# Main.net
KiCad netlist of a schematic drawn in Altium Designer
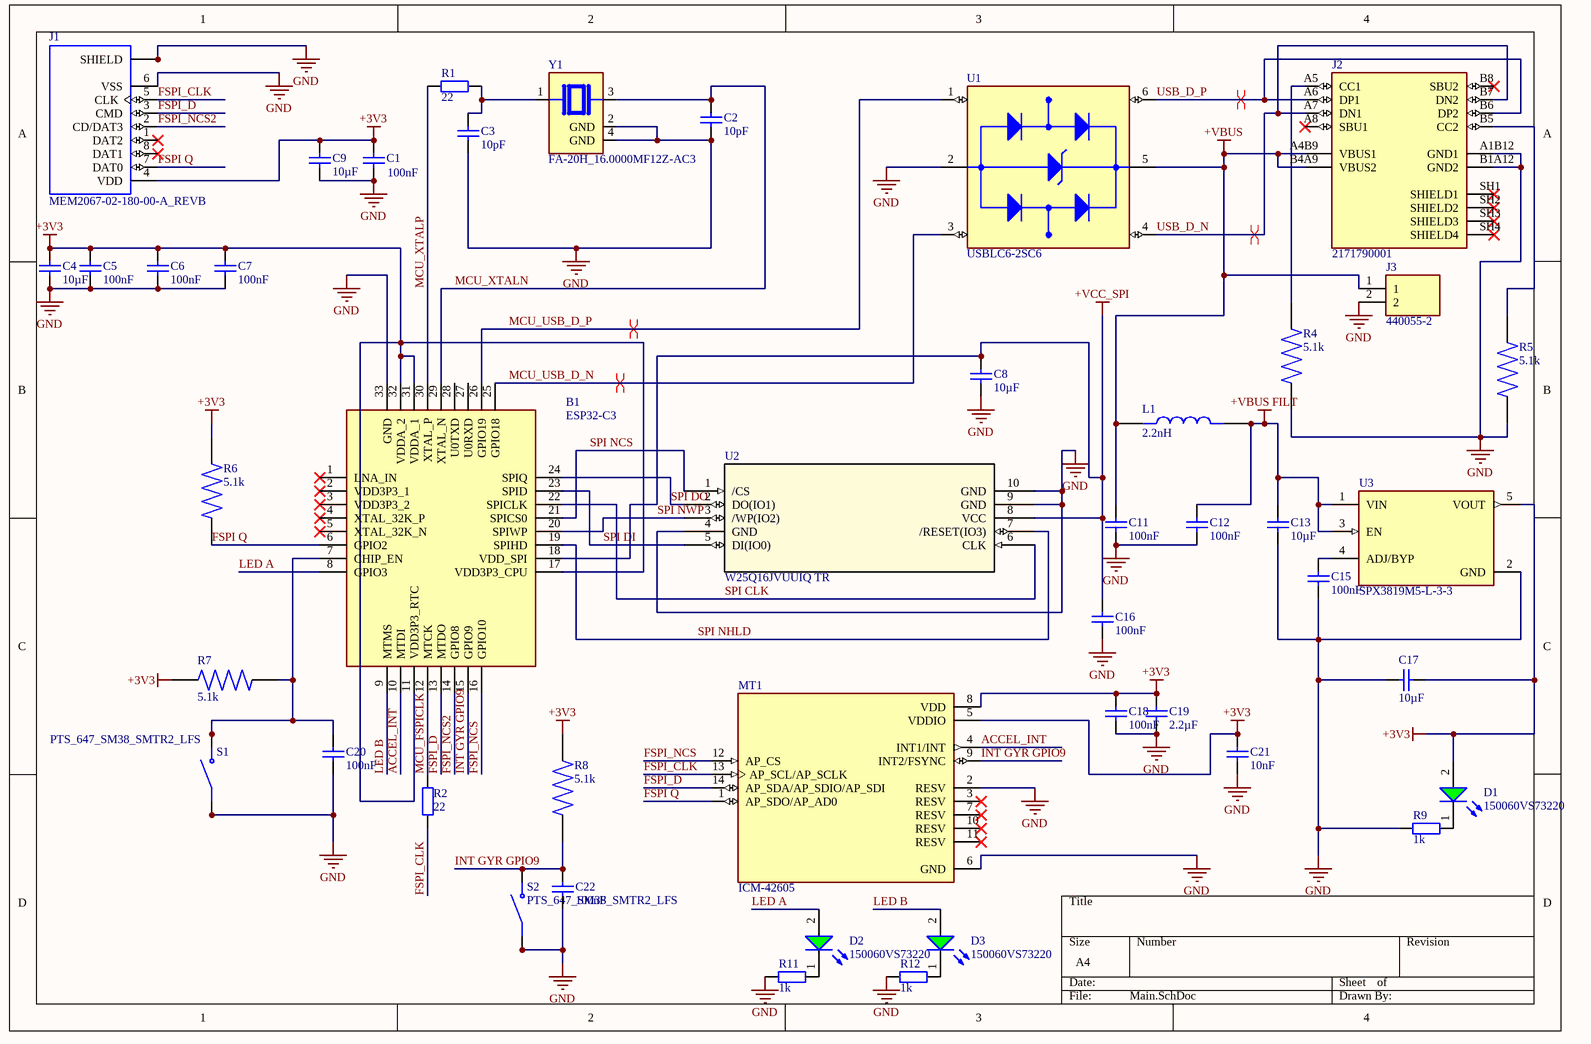
[diagram p0: Main.SchDoc]

(export (version "E")
  (design (tool "Eeschema 10.0.6"))
  (components
    (comp (ref "B1")
      (value "ESP32-C3")
      (footprint "QFN50P500X500X90-33N-D")
      (description "Ultra-Low-Power SoC with RISC-V Single-Core CPU")
      (fields (field (name "MOUSER PART NUMBER") "356-ESP32-C3"))
      (libsource (lib "EMEA - Green Bear Formula Student- Berlin University of Applied Sciences") (part "ESP32-C3"))
    )
    (comp (ref "C1")
      (value "100nF")
      (footprint "WCAP-CSGP_0805_L2W1.25H0.8_Reflow")
      (description "WCAP-CSGP Multilayer Ceramic Chip Capacitor, General Purpose, size 0805, X7R, 100nF, 10VDC")
      (fields
        (field (name "MANUFACTURER") "Wurth Elektronik")
        (field (name "MANUFACTURER PART NUMBER") "885012207016")
      )
      (libsource (lib "EMEA - Green Bear Formula Student- Berlin University of Applied Sciences") (part "885012209047R"))
    )
    (comp (ref "C2")
      (value "10pF")
      (footprint "WCAP-CSGP_1206_L3.2W1.6H0.8")
      (description "WCAP-CSGP Multilayer Ceramic Chip Capacitor, General Purpose, size 1206, NP0, 10pF, 50VDC")
      (fields
        (field (name "MANUFACTURER") "Wurth Elektronik")
        (field (name "MANUFACTURER PART NUMBER") "885012008037")
      )
      (libsource (lib "EMEA - Green Bear Formula Student- Berlin University of Applied Sciences") (part "885012209047R"))
    )
    (comp (ref "C3")
      (value "10pF")
      (footprint "WCAP-CSGP_1206_L3.2W1.6H0.8")
      (description "WCAP-CSGP Multilayer Ceramic Chip Capacitor, General Purpose, size 1206, NP0, 10pF, 50VDC")
      (fields
        (field (name "MANUFACTURER") "Wurth Elektronik")
        (field (name "MANUFACTURER PART NUMBER") "885012008037")
      )
      (libsource (lib "EMEA - Green Bear Formula Student- Berlin University of Applied Sciences") (part "885012209047R"))
    )
    (comp (ref "C4")
      (value "10µF")
      (footprint "WCAP-CSGP_1206_L3.2W1.6H1.6")
      (description "WCAP-CSGP Multilayer Ceramic Chip Capacitor, General Purpose, size 1206, X7R, 10uF, 10VDC")
      (fields
        (field (name "MANUFACTURER") "Wurth Elektronik")
        (field (name "MANUFACTURER PART NUMBER") "885012208018")
      )
      (libsource (lib "EMEA - Green Bear Formula Student- Berlin University of Applied Sciences") (part "885012209047R"))
    )
    (comp (ref "C5")
      (value "100nF")
      (footprint "WCAP-CSGP_0805_L2W1.25H0.8_Reflow")
      (description "WCAP-CSGP Multilayer Ceramic Chip Capacitor, General Purpose, size 0805, X7R, 100nF, 10VDC")
      (fields
        (field (name "MANUFACTURER") "Wurth Elektronik")
        (field (name "MANUFACTURER PART NUMBER") "885012207016")
      )
      (libsource (lib "EMEA - Green Bear Formula Student- Berlin University of Applied Sciences") (part "885012209047R"))
    )
    (comp (ref "C6")
      (value "100nF")
      (footprint "WCAP-CSGP_0805_L2W1.25H0.8_Reflow")
      (description "WCAP-CSGP Multilayer Ceramic Chip Capacitor, General Purpose, size 0805, X7R, 100nF, 10VDC")
      (fields
        (field (name "MANUFACTURER") "Wurth Elektronik")
        (field (name "MANUFACTURER PART NUMBER") "885012207016")
      )
      (libsource (lib "EMEA - Green Bear Formula Student- Berlin University of Applied Sciences") (part "885012209047R"))
    )
    (comp (ref "C7")
      (value "100nF")
      (footprint "WCAP-CSGP_0805_L2W1.25H0.8_Reflow")
      (description "WCAP-CSGP Multilayer Ceramic Chip Capacitor, General Purpose, size 0805, X7R, 100nF, 10VDC")
      (fields
        (field (name "MANUFACTURER") "Wurth Elektronik")
        (field (name "MANUFACTURER PART NUMBER") "885012207016")
      )
      (libsource (lib "EMEA - Green Bear Formula Student- Berlin University of Applied Sciences") (part "885012209047R"))
    )
    (comp (ref "C8")
      (value "10µF")
      (footprint "WCAP-CSGP_1206_L3.2W1.6H1.6")
      (description "WCAP-CSGP Multilayer Ceramic Chip Capacitor, General Purpose, size 1206, X7R, 10uF, 10VDC")
      (fields
        (field (name "MANUFACTURER") "Wurth Elektronik")
        (field (name "MANUFACTURER PART NUMBER") "885012208018")
      )
      (libsource (lib "EMEA - Green Bear Formula Student- Berlin University of Applied Sciences") (part "885012209047R"))
    )
    (comp (ref "C9")
      (value "10µF")
      (footprint "WCAP-CSGP_1206_L3.2W1.6H1.6")
      (description "WCAP-CSGP Multilayer Ceramic Chip Capacitor, General Purpose, size 1206, X7R, 10uF, 10VDC")
      (fields
        (field (name "MANUFACTURER") "Wurth Elektronik")
        (field (name "MANUFACTURER PART NUMBER") "885012208018")
      )
      (libsource (lib "EMEA - Green Bear Formula Student- Berlin University of Applied Sciences") (part "885012209047R"))
    )
    (comp (ref "C11")
      (value "100nF")
      (footprint "WCAP-CSGP_0805_L2W1.25H0.8_Reflow")
      (description "WCAP-CSGP Multilayer Ceramic Chip Capacitor, General Purpose, size 0805, X7R, 100nF, 10VDC")
      (fields
        (field (name "MANUFACTURER") "Wurth Elektronik")
        (field (name "MANUFACTURER PART NUMBER") "885012207016")
      )
      (libsource (lib "EMEA - Green Bear Formula Student- Berlin University of Applied Sciences") (part "885012209047R"))
    )
    (comp (ref "C12")
      (value "100nF")
      (footprint "WCAP-CSGP_0805_L2W1.25H0.8_Reflow")
      (description "WCAP-CSGP Multilayer Ceramic Chip Capacitor, General Purpose, size 0805, X7R, 100nF, 10VDC")
      (fields
        (field (name "MANUFACTURER") "Wurth Elektronik")
        (field (name "MANUFACTURER PART NUMBER") "885012207016")
      )
      (libsource (lib "EMEA - Green Bear Formula Student- Berlin University of Applied Sciences") (part "885012209047R"))
    )
    (comp (ref "C13")
      (value "10µF")
      (footprint "WCAP-CSGP_1206_L3.2W1.6H1.6")
      (description "WCAP-CSGP Multilayer Ceramic Chip Capacitor, General Purpose, size 1206, X7R, 10uF, 10VDC")
      (fields
        (field (name "MANUFACTURER") "Wurth Elektronik")
        (field (name "MANUFACTURER PART NUMBER") "885012208018")
      )
      (libsource (lib "EMEA - Green Bear Formula Student- Berlin University of Applied Sciences") (part "885012209047R"))
    )
    (comp (ref "C15")
      (value "100nF")
      (footprint "WCAP-CSGP_0805_L2W1.25H0.8_Reflow")
      (description "WCAP-CSGP Multilayer Ceramic Chip Capacitor, General Purpose, size 0805, X7R, 100nF, 10VDC")
      (fields
        (field (name "MANUFACTURER") "Wurth Elektronik")
        (field (name "MANUFACTURER PART NUMBER") "885012207016")
      )
      (libsource (lib "EMEA - Green Bear Formula Student- Berlin University of Applied Sciences") (part "885012209047R"))
    )
    (comp (ref "C16")
      (value "100nF")
      (footprint "WCAP-CSGP_0805_L2W1.25H0.8_Reflow")
      (description "WCAP-CSGP Multilayer Ceramic Chip Capacitor, General Purpose, size 0805, X7R, 100nF, 10VDC")
      (fields
        (field (name "MANUFACTURER") "Wurth Elektronik")
        (field (name "MANUFACTURER PART NUMBER") "885012207016")
      )
      (libsource (lib "EMEA - Green Bear Formula Student- Berlin University of Applied Sciences") (part "885012209047R"))
    )
    (comp (ref "C17")
      (value "10µF")
      (footprint "WCAP-CSGP_1206_L3.2W1.6H1.6")
      (description "WCAP-CSGP Multilayer Ceramic Chip Capacitor, General Purpose, size 1206, X7R, 10uF, 10VDC")
      (fields
        (field (name "MANUFACTURER") "Wurth Elektronik")
        (field (name "MANUFACTURER PART NUMBER") "885012208018")
      )
      (libsource (lib "EMEA - Green Bear Formula Student- Berlin University of Applied Sciences") (part "885012209047R"))
    )
    (comp (ref "C18")
      (value "100nF")
      (footprint "WCAP-CSGP_0805_L2W1.25H0.8_Reflow")
      (description "WCAP-CSGP Multilayer Ceramic Chip Capacitor, General Purpose, size 0805, X7R, 100nF, 10VDC")
      (fields
        (field (name "MANUFACTURER") "Wurth Elektronik")
        (field (name "MANUFACTURER PART NUMBER") "885012207016")
      )
      (libsource (lib "EMEA - Green Bear Formula Student- Berlin University of Applied Sciences") (part "885012209047R"))
    )
    (comp (ref "C19")
      (value "2.2µF")
      (footprint "WCAP-CSGP_0805_L2W1.25H1.25")
      (description "WCAP-CSGP Multilayer Ceramic Chip Capacitor, General Purpose, size 0805, X5R, 2.2uF, 16VDC")
      (fields
        (field (name "MANUFACTURER PART NUMBER") "885012107012")
        (field (name "MANUFACTURER") "Wurth Elektronik")
      )
      (libsource (lib "EMEA - Green Bear Formula Student- Berlin University of Applied Sciences") (part "885012209047R"))
    )
    (comp (ref "C20")
      (value "100nF")
      (footprint "WCAP-CSGP_0805_L2W1.25H0.8_Reflow")
      (description "WCAP-CSGP Multilayer Ceramic Chip Capacitor, General Purpose, size 0805, X7R, 100nF, 10VDC")
      (fields
        (field (name "MANUFACTURER") "Wurth Elektronik")
        (field (name "MANUFACTURER PART NUMBER") "885012207016")
      )
      (libsource (lib "EMEA - Green Bear Formula Student- Berlin University of Applied Sciences") (part "885012209047R"))
    )
    (comp (ref "C21")
      (value "10nF")
      (footprint "WCAP-CSGP_0805_L2W1.25H1.25")
      (description "WCAP-CSGP Multilayer Ceramic Chip Capacitor, General Purpose, size 0805, NP0, 10nF, 10VDC")
      (fields
        (field (name "MANUFACTURER") "Wurth Elektronik")
        (field (name "MANUFACTURER PART NUMBER") "885012007009")
      )
      (libsource (lib "EMEA - Green Bear Formula Student- Berlin University of Applied Sciences") (part "885012209047R"))
    )
    (comp (ref "C22")
      (value "100nF")
      (footprint "WCAP-CSGP_0805_L2W1.25H0.8_Reflow")
      (description "WCAP-CSGP Multilayer Ceramic Chip Capacitor, General Purpose, size 0805, X7R, 100nF, 10VDC")
      (fields
        (field (name "MANUFACTURER") "Wurth Elektronik")
        (field (name "MANUFACTURER PART NUMBER") "885012207016")
      )
      (libsource (lib "EMEA - Green Bear Formula Student- Berlin University of Applied Sciences") (part "885012209047R"))
    )
    (comp (ref "D1")
      (value "150060VS73220")
      (footprint "WL-SMCC_0603_L1.6W0.8H0.2")
      (description "WL-SMCC Mono-color Chip LED Compact, size 0603, Bright Green, 2V, 120°")
      (fields (field (name "MANUFACTURER") "Wurth Elektronik"))
      (libsource (lib "EMEA - Green Bear Formula Student- Berlin University of Applied Sciences") (part "150060VS73220"))
    )
    (comp (ref "D2")
      (value "150060VS73220")
      (footprint "WL-SMCC_0603_L1.6W0.8H0.2")
      (description "WL-SMCC Mono-color Chip LED Compact, size 0603, Bright Green, 2V, 120°")
      (fields (field (name "MANUFACTURER") "Wurth Elektronik"))
      (libsource (lib "EMEA - Green Bear Formula Student- Berlin University of Applied Sciences") (part "150060VS73220"))
    )
    (comp (ref "D3")
      (value "150060VS73220")
      (footprint "WL-SMCC_0603_L1.6W0.8H0.2")
      (description "WL-SMCC Mono-color Chip LED Compact, size 0603, Bright Green, 2V, 120°")
      (fields (field (name "MANUFACTURER") "Wurth Elektronik"))
      (libsource (lib "EMEA - Green Bear Formula Student- Berlin University of Applied Sciences") (part "150060VS73220"))
    )
    (comp (ref "J1")
      (value "MEM2067-02-180-00-A_REVB")
      (footprint "GCT_MEM2067-02-180-00-A_REVB")
      (description "Micro SD Memory Card ConnectorSMT, Hinged, 1.80mm Profile")
      (libsource (lib "EMEA - Green Bear Formula Student- Berlin University of Applied Sciences") (part "MEM2067-02-180-00-A_REVB"))
    )
    (comp (ref "J2")
      (value "2171790001")
      (footprint "MOLEX_2171790001")
      (description "USB Type C - Connector, Top-mount SMT, 16pos")
      (fields (field (name "MF") "Molex") (field (name "MP") "217179-0001"))
      (libsource (lib "EMEA - Green Bear Formula Student- Berlin University of Applied Sciences") (part "2171790001"))
    )
    (comp (ref "J3")
      (value "440055-2")
      (footprint "TE_440055-2")
      (description "2.0MM,HDR,2POS,R/A")
      (fields (field (name "MF") "TE Connectivity"))
      (libsource (lib "EMEA - Green Bear Formula Student- Berlin University of Applied Sciences") (part "440055-2"))
    )
    (comp (ref "L1")
      (value "2.2nH")
      (footprint "INDC0402X22N")
      (description "2.2 nH Shielded Multilayer Inductor 400 mA 400mOhm Max 01005 (0402 Metric)")
      (fields
        (field (name "MP") "MHQ0402PSA2N2BT000")
        (field (name "MF") "{'manufacturer': u'TDK Corporation'}")
      )
      (libsource (lib "EMEA - Green Bear Formula Student- Berlin University of Applied Sciences") (part "MHQ0402PSA2N2BT000"))
    )
    (comp (ref "MT1")
      (value "ICM-42605")
      (footprint "XDCR_ICM-42605")
      (libsource (lib "EMEA - Green Bear Formula Student- Berlin University of Applied Sciences") (part "ICM-42605"))
    )
    (comp (ref "R1")
      (value "22")
      (footprint "WRIS-RSKS_0603_Reflow")
      (description "WRIS-RSKS Thick Film Resistor, size 0603, 22Ohm, 100mW")
      (fields
        (field (name "MANUFACTURER") "Wurth Elektronik")
        (field (name "MANUFACTURER PART NUMBER") "560112116043")
      )
      (libsource (lib "EMEA - Green Bear Formula Student- Berlin University of Applied Sciences") (part "560112140010"))
    )
    (comp (ref "R2")
      (value "22")
      (footprint "WRIS-RSKS_0603_Reflow")
      (description "WRIS-RSKS Thick Film Resistor, size 0603, 22Ohm, 100mW")
      (fields
        (field (name "MANUFACTURER") "Wurth Elektronik")
        (field (name "MANUFACTURER PART NUMBER") "560112116043")
      )
      (libsource (lib "") (part "560112140010_1"))
    )
    (comp (ref "R4")
      (value "5.1k")
      (footprint "RESC2012X60N")
      (description "RC0805 5,1K 5% 0,125W")
      (fields (field (name "MP") "RC0805JR-075K1L"))
      (libsource (lib "EMEA - Green Bear Formula Student- Berlin University of Applied Sciences") (part "RC0805JR-075K1L"))
    )
    (comp (ref "R5")
      (value "5.1k")
      (footprint "RESC2012X60N")
      (description "RC0805 5,1K 5% 0,125W")
      (fields (field (name "MP") "RC0805JR-075K1L"))
      (libsource (lib "EMEA - Green Bear Formula Student- Berlin University of Applied Sciences") (part "RC0805JR-075K1L"))
    )
    (comp (ref "R6")
      (value "5.1k")
      (footprint "RESC2012X60N")
      (description "RC0805 5,1K 5% 0,125W")
      (fields (field (name "MP") "RC0805JR-075K1L"))
      (libsource (lib "EMEA - Green Bear Formula Student- Berlin University of Applied Sciences") (part "RC0805JR-075K1L"))
    )
    (comp (ref "R7")
      (value "5.1k")
      (footprint "RESC2012X60N")
      (description "RC0805 5,1K 5% 0,125W")
      (fields (field (name "MP") "RC0805JR-075K1L"))
      (libsource (lib "EMEA - Green Bear Formula Student- Berlin University of Applied Sciences") (part "RC0805JR-075K1L"))
    )
    (comp (ref "R8")
      (value "5.1k")
      (footprint "RESC2012X60N")
      (description "RC0805 5,1K 5% 0,125W")
      (fields (field (name "MP") "RC0805JR-075K1L"))
      (libsource (lib "EMEA - Green Bear Formula Student- Berlin University of Applied Sciences") (part "RC0805JR-075K1L"))
    )
    (comp (ref "R9")
      (value "1k")
      (footprint "WRIS-RSKS_0603_Reflow")
      (description "WRIS-RSKS Thick Film Resistor, size 0603, 1000Ohm, 100mW")
      (fields
        (field (name "MANUFACTURER PART NUMBER") "560112116014")
        (field (name "MANUFACTURER") "Wurth Elektronik")
      )
      (libsource (lib "EMEA - Green Bear Formula Student- Berlin University of Applied Sciences") (part "560112140010"))
    )
    (comp (ref "R11")
      (value "1k")
      (footprint "WRIS-RSKS_0603_Reflow")
      (description "WRIS-RSKS Thick Film Resistor, size 0603, 1000Ohm, 100mW")
      (fields
        (field (name "MANUFACTURER PART NUMBER") "560112116014")
        (field (name "MANUFACTURER") "Wurth Elektronik")
      )
      (libsource (lib "EMEA - Green Bear Formula Student- Berlin University of Applied Sciences") (part "560112140010"))
    )
    (comp (ref "R12")
      (value "1k")
      (footprint "WRIS-RSKS_0603_Reflow")
      (description "WRIS-RSKS Thick Film Resistor, size 0603, 1000Ohm, 100mW")
      (fields
        (field (name "MANUFACTURER PART NUMBER") "560112116014")
        (field (name "MANUFACTURER") "Wurth Elektronik")
      )
      (libsource (lib "EMEA - Green Bear Formula Student- Berlin University of Applied Sciences") (part "560112140010"))
    )
    (comp (ref "S1")
      (value "PTS_647_SM38_SMTR2_LFS")
      (footprint "SW_PTS_647_SM38_SMTR2_LFS")
      (description "Tactile Switch SPST-NO Top Actuated Surface Mount")
      (fields (field (name "MF") "C&K") (field (name "DIGI-KEY_PART_NUMBER") "PTS647SM38SMTR2LFSTR-ND"))
      (libsource (lib "EMEA - Green Bear Formula Student- Berlin University of Applied Sciences") (part "PTS_647_SM38_SMTR2_LFS"))
    )
    (comp (ref "S2")
      (value "PTS_647_SM38_SMTR2_LFS")
      (footprint "SW_PTS_647_SM38_SMTR2_LFS")
      (description "Tactile Switch SPST-NO Top Actuated Surface Mount")
      (fields (field (name "MF") "C&K") (field (name "DIGI-KEY_PART_NUMBER") "PTS647SM38SMTR2LFSTR-ND"))
      (libsource (lib "EMEA - Green Bear Formula Student- Berlin University of Applied Sciences") (part "PTS_647_SM38_SMTR2_LFS"))
    )
    (comp (ref "U1")
      (value "USBLC6-2SC6")
      (footprint "SOT95P280X145-6N")
      (description "17V Clamp 5A (8/20Âµs) Ipp Tvs Diode Surface Mount SOT-23-6")
      (fields (field (name "MF") "STMicroelectronics"))
      (libsource (lib "EMEA - Green Bear Formula Student- Berlin University of Applied Sciences") (part "USBLC6-2SC6"))
    )
    (comp (ref "U2")
      (value "W25Q16JVUUIQ TR")
      (footprint "USON8_4X3_UU_WIN")
      (description "No Description Available")
      (libsource (lib "EMEA - Green Bear Formula Student- Berlin University of Applied Sciences") (part "W25Q16JVUUIQ TR"))
    )
    (comp (ref "U3")
      (value "SPX3819M5-L-3-3")
      (footprint "SOT95P280X145-5N")
      (description "Linear Voltage Regulator IC Positive Fixed 1 Output 500mA SOT-23-5")
      (fields (field (name "MF") "MaxLinear, Inc.") (field (name "MP") "SPX3819M5-L-3-3/TR"))
      (libsource (lib "EMEA - Green Bear Formula Student- Berlin University of Applied Sciences") (part "SPX3819M5-L-3-3"))
    )
    (comp (ref "Y1")
      (value "FA-20H_16.0000MF12Z-AC3")
      (footprint "XTAL_FA-20H_16.0000MF12Z-AC3")
      (description "16 MHz Â±10ppm Crystal 9pF 80 Ohms 4-SMD, No Lead")
      (fields (field (name "MP") "FA-20H 16.0000MF12Z-AC3") (field (name "MF") "EPSON"))
      (libsource (lib "EMEA - Green Bear Formula Student- Berlin University of Applied Sciences") (part "FA-20H_16.0000MF12Z-AC3"))
    )
  )
  (nets
    (net (code "1") (name "+3V3") (class "Default")
      (node (ref "B1") (pin "11") (pinfunction "VDD3P3_RTC_11") (pintype "passive"))
      (node (ref "B1") (pin "17") (pinfunction "VDD3P3_CPU_17") (pintype "passive"))
      (node (ref "B1") (pin "31") (pinfunction "VDDA_1_31") (pintype "passive"))
      (node (ref "B1") (pin "32") (pinfunction "VDDA_2_32") (pintype "passive"))
      (node (ref "C1") (pin "2") (pinfunction "2_2") (pintype "passive"))
      (node (ref "C17") (pin "1") (pinfunction "1_1") (pintype "passive"))
      (node (ref "C18") (pin "2") (pinfunction "2_2") (pintype "passive"))
      (node (ref "C19") (pin "2") (pinfunction "2_2") (pintype "passive"))
      (node (ref "C21") (pin "2") (pinfunction "2_2") (pintype "passive"))
      (node (ref "C4") (pin "2") (pinfunction "2_2") (pintype "passive"))
      (node (ref "C5") (pin "2") (pinfunction "2_2") (pintype "passive"))
      (node (ref "C6") (pin "2") (pinfunction "2_2") (pintype "passive"))
      (node (ref "C7") (pin "2") (pinfunction "2_2") (pintype "passive"))
      (node (ref "C9") (pin "2") (pinfunction "2_2") (pintype "passive"))
      (node (ref "D1") (pin "2") (pinfunction "A_2") (pintype "passive"))
      (node (ref "J1") (pin "4") (pinfunction "VDD_4") (pintype "power_in"))
      (node (ref "MT1") (pin "5") (pinfunction "VDDIO_5") (pintype "power_in"))
      (node (ref "MT1") (pin "8") (pinfunction "VDD_8") (pintype "power_in"))
      (node (ref "R6") (pin "1") (pinfunction "1_1") (pintype "passive"))
      (node (ref "R7") (pin "1") (pinfunction "1_1") (pintype "passive"))
      (node (ref "R8") (pin "2") (pinfunction "2_2") (pintype "passive"))
      (node (ref "U3") (pin "5") (pinfunction "VOUT_5") (pintype "output"))
    )
    (net (code "2") (name "+VBUS") (class "Default")
      (node (ref "C11") (pin "2") (pinfunction "2_2") (pintype "passive"))
      (node (ref "J2") (pin "A4B9") (pinfunction "VBUS1_A4B9") (pintype "power_in"))
      (node (ref "J2") (pin "B4A9") (pinfunction "VBUS2_B4A9") (pintype "power_in"))
      (node (ref "J3") (pin "1") (pinfunction "1_1") (pintype "passive"))
      (node (ref "L1") (pin "1") (pinfunction "1_1") (pintype "passive"))
      (node (ref "U1") (pin "5") (pinfunction "VBUS_5") (pintype "power_in"))
    )
    (net (code "3") (name "+VBUS FILT") (class "Default")
      (node (ref "C12") (pin "2") (pinfunction "2_2") (pintype "passive"))
      (node (ref "C13") (pin "2") (pinfunction "2_2") (pintype "passive"))
      (node (ref "L1") (pin "2") (pinfunction "2_2") (pintype "passive"))
      (node (ref "U3") (pin "1") (pinfunction "VIN_1") (pintype "power_in"))
      (node (ref "U3") (pin "3") (pinfunction "EN_3") (pintype "input"))
    )
    (net (code "4") (name "+VCC_SPI") (class "Default")
      (node (ref "B1") (pin "18") (pinfunction "VDD_SPI_18") (pintype "passive"))
      (node (ref "C16") (pin "2") (pinfunction "2_2") (pintype "passive"))
      (node (ref "C8") (pin "2") (pinfunction "2_2") (pintype "passive"))
      (node (ref "U2") (pin "8") (pinfunction "VCC_8") (pintype "power_in"))
    )
    (net (code "5") (name "/ACCEL_INT") (class "Default")
      (node (ref "B1") (pin "10") (pinfunction "MTDI_10") (pintype "passive"))
      (node (ref "MT1") (pin "4") (pinfunction "INT1/INT_4") (pintype "output"))
    )
    (net (code "6") (name "/FSPI Q") (class "Default")
      (node (ref "B1") (pin "6") (pinfunction "GPIO2_6") (pintype "passive"))
      (node (ref "J1") (pin "7") (pinfunction "DAT0_7") (pintype "bidirectional"))
      (node (ref "MT1") (pin "1") (pinfunction "AP_SDO/AP_AD0_1") (pintype "bidirectional"))
      (node (ref "R6") (pin "2") (pinfunction "2_2") (pintype "passive"))
    )
    (net (code "7") (name "/FSPI_CLK") (class "Default")
      (node (ref "J1") (pin "5") (pinfunction "CLK_5") (pintype "bidirectional"))
      (node (ref "MT1") (pin "13") (pinfunction "AP_SCL/AP_SCLK_13") (pintype "input"))
      (node (ref "R2") (pin "1") (pinfunction "1_1") (pintype "passive"))
    )
    (net (code "8") (name "/FSPI_D") (class "Default")
      (node (ref "B1") (pin "13") (pinfunction "MTDO_13") (pintype "passive"))
      (node (ref "J1") (pin "3") (pinfunction "CMD_3") (pintype "bidirectional"))
      (node (ref "MT1") (pin "14") (pinfunction "AP_SDA/AP_SDIO/AP_SDI_14") (pintype "bidirectional"))
    )
    (net (code "9") (name "/FSPI_NCS") (class "Default")
      (node (ref "B1") (pin "16") (pinfunction "GPIO10_16") (pintype "passive"))
      (node (ref "MT1") (pin "12") (pinfunction "AP_CS_12") (pintype "input"))
    )
    (net (code "10") (name "/FSPI_NCS2") (class "Default")
      (node (ref "B1") (pin "14") (pinfunction "GPIO8_14") (pintype "passive"))
      (node (ref "J1") (pin "2") (pinfunction "CD/DAT3_2") (pintype "bidirectional"))
    )
    (net (code "11") (name "/INT GYR GPIO9") (class "Default")
      (node (ref "B1") (pin "15") (pinfunction "GPIO9_15") (pintype "passive"))
      (node (ref "C22") (pin "2") (pinfunction "2_2") (pintype "passive"))
      (node (ref "MT1") (pin "9") (pinfunction "INT2/FSYNC_9") (pintype "bidirectional"))
      (node (ref "R8") (pin "1") (pinfunction "1_1") (pintype "passive"))
      (node (ref "S2") (pin "1") (pinfunction "NO_1") (pintype "passive"))
      (node (ref "S2") (pin "2") (pinfunction "NO_2") (pintype "passive"))
    )
    (net (code "12") (name "/LED A") (class "Default")
      (node (ref "B1") (pin "8") (pinfunction "GPIO3_8") (pintype "passive"))
      (node (ref "D2") (pin "2") (pinfunction "A_2") (pintype "passive"))
    )
    (net (code "13") (name "/LED B") (class "Default")
      (node (ref "B1") (pin "9") (pinfunction "MTMS_9") (pintype "passive"))
      (node (ref "D3") (pin "2") (pinfunction "A_2") (pintype "passive"))
    )
    (net (code "14") (name "/MCU_FSPICLK") (class "Default")
      (node (ref "B1") (pin "12") (pinfunction "MTCK_12") (pintype "passive"))
      (node (ref "R2") (pin "2") (pinfunction "2_2") (pintype "passive"))
    )
    (net (code "15") (name "/MCU_USB_D_N") (class "Default")
      (node (ref "B1") (pin "25") (pinfunction "GPIO18_25") (pintype "passive"))
      (node (ref "U1") (pin "3") (pinfunction "I/O2_IN_3") (pintype "bidirectional"))
    )
    (net (code "16") (name "/MCU_USB_D_P") (class "Default")
      (node (ref "B1") (pin "26") (pinfunction "GPIO19_26") (pintype "passive"))
      (node (ref "U1") (pin "1") (pinfunction "I/O1_IN_1") (pintype "bidirectional"))
    )
    (net (code "17") (name "/MCU_XTALN") (class "Default")
      (node (ref "B1") (pin "29") (pinfunction "XTAL_N_29") (pintype "passive"))
      (node (ref "C2") (pin "1") (pinfunction "1_1") (pintype "passive"))
      (node (ref "Y1") (pin "3") (pinfunction "2_3") (pintype "passive"))
    )
    (net (code "18") (name "/MCU_XTALP") (class "Default")
      (node (ref "B1") (pin "30") (pinfunction "XTAL_P_30") (pintype "passive"))
      (node (ref "R1") (pin "1") (pinfunction "1_1") (pintype "passive"))
    )
    (net (code "19") (name "/SPI CLK") (class "Default")
      (node (ref "B1") (pin "22") (pinfunction "SPICLK_22") (pintype "passive"))
      (node (ref "U2") (pin "6") (pinfunction "CLK_6") (pintype "input"))
    )
    (net (code "20") (name "/SPI DI") (class "Default")
      (node (ref "B1") (pin "23") (pinfunction "SPID_23") (pintype "passive"))
      (node (ref "U2") (pin "5") (pinfunction "DI(IO0)_5") (pintype "bidirectional"))
    )
    (net (code "21") (name "/SPI DO") (class "Default")
      (node (ref "B1") (pin "24") (pinfunction "SPIQ_24") (pintype "passive"))
      (node (ref "U2") (pin "2") (pinfunction "DO(IO1)_2") (pintype "bidirectional"))
    )
    (net (code "22") (name "/SPI NCS") (class "Default")
      (node (ref "B1") (pin "21") (pinfunction "SPICS0_21") (pintype "passive"))
      (node (ref "U2") (pin "1") (pinfunction "/CS_1") (pintype "input"))
    )
    (net (code "23") (name "/SPI NHLD") (class "Default")
      (node (ref "B1") (pin "19") (pinfunction "SPIHD_19") (pintype "passive"))
      (node (ref "U2") (pin "7") (pinfunction "/RESET(IO3)_7") (pintype "bidirectional"))
    )
    (net (code "24") (name "/SPI NWP") (class "Default")
      (node (ref "B1") (pin "20") (pinfunction "SPIWP_20") (pintype "passive"))
      (node (ref "U2") (pin "3") (pinfunction "/WP(IO2)_3") (pintype "bidirectional"))
    )
    (net (code "25") (name "/USB_D_N") (class "Default")
      (node (ref "J2") (pin "A7") (pinfunction "DN1_A7") (pintype "bidirectional"))
      (node (ref "J2") (pin "B7") (pinfunction "DN2_B7") (pintype "bidirectional"))
      (node (ref "U1") (pin "4") (pinfunction "I/O2_OUT_4") (pintype "bidirectional"))
    )
    (net (code "26") (name "/USB_D_P") (class "Default")
      (node (ref "J2") (pin "A6") (pinfunction "DP1_A6") (pintype "bidirectional"))
      (node (ref "J2") (pin "B6") (pinfunction "DP2_B6") (pintype "bidirectional"))
      (node (ref "U1") (pin "6") (pinfunction "I/O1_OUT_6") (pintype "bidirectional"))
    )
    (net (code "27") (name "GND") (class "Default")
      (node (ref "B1") (pin "33") (pinfunction "GND_33") (pintype "passive"))
      (node (ref "C1") (pin "1") (pinfunction "1_1") (pintype "passive"))
      (node (ref "C11") (pin "1") (pinfunction "1_1") (pintype "passive"))
      (node (ref "C12") (pin "1") (pinfunction "1_1") (pintype "passive"))
      (node (ref "C13") (pin "1") (pinfunction "1_1") (pintype "passive"))
      (node (ref "C15") (pin "1") (pinfunction "1_1") (pintype "passive"))
      (node (ref "C16") (pin "1") (pinfunction "1_1") (pintype "passive"))
      (node (ref "C17") (pin "2") (pinfunction "2_2") (pintype "passive"))
      (node (ref "C18") (pin "1") (pinfunction "1_1") (pintype "passive"))
      (node (ref "C19") (pin "1") (pinfunction "1_1") (pintype "passive"))
      (node (ref "C2") (pin "2") (pinfunction "2_2") (pintype "passive"))
      (node (ref "C20") (pin "1") (pinfunction "1_1") (pintype "passive"))
      (node (ref "C21") (pin "1") (pinfunction "1_1") (pintype "passive"))
      (node (ref "C22") (pin "1") (pinfunction "1_1") (pintype "passive"))
      (node (ref "C3") (pin "2") (pinfunction "2_2") (pintype "passive"))
      (node (ref "C4") (pin "1") (pinfunction "1_1") (pintype "passive"))
      (node (ref "C5") (pin "1") (pinfunction "1_1") (pintype "passive"))
      (node (ref "C6") (pin "1") (pinfunction "1_1") (pintype "passive"))
      (node (ref "C7") (pin "1") (pinfunction "1_1") (pintype "passive"))
      (node (ref "C8") (pin "1") (pinfunction "1_1") (pintype "passive"))
      (node (ref "C9") (pin "1") (pinfunction "1_1") (pintype "passive"))
      (node (ref "J1") (pin "10") (pinfunction "SHIELD_10") (pintype "passive"))
      (node (ref "J1") (pin "11") (pinfunction "SHIELD_11") (pintype "passive"))
      (node (ref "J1") (pin "12") (pinfunction "SHIELD_12") (pintype "passive"))
      (node (ref "J1") (pin "6") (pinfunction "VSS_6") (pintype "power_in"))
      (node (ref "J1") (pin "9") (pinfunction "SHIELD_9") (pintype "passive"))
      (node (ref "J2") (pin "A1B12") (pinfunction "GND1_A1B12") (pintype "power_in"))
      (node (ref "J2") (pin "B1A12") (pinfunction "GND2_B1A12") (pintype "power_in"))
      (node (ref "J3") (pin "2") (pinfunction "2_2") (pintype "passive"))
      (node (ref "MT1") (pin "2") (pinfunction "RESV_2") (pintype "passive"))
      (node (ref "MT1") (pin "6") (pinfunction "GND_6") (pintype "power_in"))
      (node (ref "R11") (pin "1") (pinfunction "1_1") (pintype "passive"))
      (node (ref "R12") (pin "1") (pinfunction "1_1") (pintype "passive"))
      (node (ref "R4") (pin "1") (pinfunction "1_1") (pintype "passive"))
      (node (ref "R5") (pin "1") (pinfunction "1_1") (pintype "passive"))
      (node (ref "R9") (pin "1") (pinfunction "1_1") (pintype "passive"))
      (node (ref "S1") (pin "3") (pinfunction "COM_3") (pintype "passive"))
      (node (ref "S1") (pin "4") (pinfunction "COM_4") (pintype "passive"))
      (node (ref "S2") (pin "3") (pinfunction "COM_3") (pintype "passive"))
      (node (ref "S2") (pin "4") (pinfunction "COM_4") (pintype "passive"))
      (node (ref "U1") (pin "2") (pinfunction "GND_2") (pintype "power_in"))
      (node (ref "U2") (pin "10") (pinfunction "GND_10") (pintype "power_in"))
      (node (ref "U2") (pin "4") (pinfunction "GND_4") (pintype "power_in"))
      (node (ref "U2") (pin "9") (pinfunction "GND_9") (pintype "power_in"))
      (node (ref "U3") (pin "2") (pinfunction "GND_2") (pintype "passive"))
      (node (ref "Y1") (pin "2") (pinfunction "GND_2") (pintype "power_in"))
      (node (ref "Y1") (pin "4") (pinfunction "GND_4") (pintype "power_in"))
    )
    (net (code "28") (name "Net-(B1-CHIP_EN)") (class "Default")
      (node (ref "B1") (pin "7") (pinfunction "CHIP_EN_7") (pintype "passive"))
      (node (ref "C20") (pin "2") (pinfunction "2_2") (pintype "passive"))
      (node (ref "R7") (pin "2") (pinfunction "2_2") (pintype "passive"))
      (node (ref "S1") (pin "1") (pinfunction "NO_1") (pintype "passive"))
      (node (ref "S1") (pin "2") (pinfunction "NO_2") (pintype "passive"))
    )
    (net (code "29") (name "Net-(C3-Pad1)") (class "Default")
      (node (ref "C3") (pin "1") (pinfunction "1_1") (pintype "passive"))
      (node (ref "R1") (pin "2") (pinfunction "2_2") (pintype "passive"))
      (node (ref "Y1") (pin "1") (pinfunction "1_1") (pintype "passive"))
    )
    (net (code "30") (name "Net-(D1-K)") (class "Default")
      (node (ref "D1") (pin "1") (pinfunction "K_1") (pintype "passive"))
      (node (ref "R9") (pin "2") (pinfunction "2_2") (pintype "passive"))
    )
    (net (code "31") (name "Net-(D2-K)") (class "Default")
      (node (ref "D2") (pin "1") (pinfunction "K_1") (pintype "passive"))
      (node (ref "R11") (pin "2") (pinfunction "2_2") (pintype "passive"))
    )
    (net (code "32") (name "Net-(D3-K)") (class "Default")
      (node (ref "D3") (pin "1") (pinfunction "K_1") (pintype "passive"))
      (node (ref "R12") (pin "2") (pinfunction "2_2") (pintype "passive"))
    )
    (net (code "33") (name "Net-(J2-CC1)") (class "Default")
      (node (ref "J2") (pin "A5") (pinfunction "CC1_A5") (pintype "bidirectional"))
      (node (ref "R4") (pin "2") (pinfunction "2_2") (pintype "passive"))
    )
    (net (code "34") (name "Net-(J2-CC2)") (class "Default")
      (node (ref "J2") (pin "B5") (pinfunction "CC2_B5") (pintype "bidirectional"))
      (node (ref "R5") (pin "2") (pinfunction "2_2") (pintype "passive"))
    )
    (net (code "35") (name "Net-(U3-ADJ{slash}BYP)") (class "Default")
      (node (ref "C15") (pin "2") (pinfunction "2_2") (pintype "passive"))
      (node (ref "U3") (pin "4") (pinfunction "ADJ/BYP_4") (pintype "passive"))
    )
    (net (code "36") (name "unconnected-(B1-LNA_IN-Pad1)") (class "Default")
      (node (ref "B1") (pin "1") (pinfunction "LNA_IN_1") (pintype "passive+no_connect"))
    )
    (net (code "37") (name "unconnected-(B1-U0RXD-Pad27)") (class "Default")
      (node (ref "B1") (pin "27") (pinfunction "U0RXD_27") (pintype "passive"))
    )
    (net (code "38") (name "unconnected-(B1-U0TXD-Pad28)") (class "Default")
      (node (ref "B1") (pin "28") (pinfunction "U0TXD_28") (pintype "passive"))
    )
    (net (code "39") (name "unconnected-(B1-VDD3P3_1-Pad2)") (class "Default")
      (node (ref "B1") (pin "2") (pinfunction "VDD3P3_1_2") (pintype "passive+no_connect"))
    )
    (net (code "40") (name "unconnected-(B1-VDD3P3_2-Pad3)") (class "Default")
      (node (ref "B1") (pin "3") (pinfunction "VDD3P3_2_3") (pintype "passive+no_connect"))
    )
    (net (code "41") (name "unconnected-(B1-XTAL_32K_N-Pad5)") (class "Default")
      (node (ref "B1") (pin "5") (pinfunction "XTAL_32K_N_5") (pintype "passive+no_connect"))
    )
    (net (code "42") (name "unconnected-(B1-XTAL_32K_P-Pad4)") (class "Default")
      (node (ref "B1") (pin "4") (pinfunction "XTAL_32K_P_4") (pintype "passive+no_connect"))
    )
    (net (code "43") (name "unconnected-(J1-DAT1-Pad8)") (class "Default")
      (node (ref "J1") (pin "8") (pinfunction "DAT1_8") (pintype "bidirectional+no_connect"))
    )
    (net (code "44") (name "unconnected-(J1-DAT2-Pad1)") (class "Default")
      (node (ref "J1") (pin "1") (pinfunction "DAT2_1") (pintype "bidirectional+no_connect"))
    )
    (net (code "45") (name "unconnected-(J2-SBU1-PadA8)") (class "Default")
      (node (ref "J2") (pin "A8") (pinfunction "SBU1_A8") (pintype "bidirectional+no_connect"))
    )
    (net (code "46") (name "unconnected-(J2-SBU2-PadB8)") (class "Default")
      (node (ref "J2") (pin "B8") (pinfunction "SBU2_B8") (pintype "bidirectional+no_connect"))
    )
    (net (code "47") (name "unconnected-(J2-SHIELD1-PadSH1)") (class "Default")
      (node (ref "J2") (pin "SH1") (pinfunction "SHIELD1_SH1") (pintype "passive+no_connect"))
    )
    (net (code "48") (name "unconnected-(J2-SHIELD2-PadSH2)") (class "Default")
      (node (ref "J2") (pin "SH2") (pinfunction "SHIELD2_SH2") (pintype "passive+no_connect"))
    )
    (net (code "49") (name "unconnected-(J2-SHIELD3-PadSH3)") (class "Default")
      (node (ref "J2") (pin "SH3") (pinfunction "SHIELD3_SH3") (pintype "passive+no_connect"))
    )
    (net (code "50") (name "unconnected-(J2-SHIELD4-PadSH4)") (class "Default")
      (node (ref "J2") (pin "SH4") (pinfunction "SHIELD4_SH4") (pintype "passive+no_connect"))
    )
    (net (code "51") (name "unconnected-(MT1-RESV-Pad3)") (class "Default")
      (node (ref "MT1") (pin "3") (pinfunction "RESV_3") (pintype "passive+no_connect"))
    )
    (net (code "52") (name "unconnected-(MT1-RESV-Pad7)") (class "Default")
      (node (ref "MT1") (pin "7") (pinfunction "RESV_7") (pintype "passive+no_connect"))
    )
    (net (code "53") (name "unconnected-(MT1-RESV-Pad10)") (class "Default")
      (node (ref "MT1") (pin "10") (pinfunction "RESV_10") (pintype "passive+no_connect"))
    )
    (net (code "54") (name "unconnected-(MT1-RESV-Pad11)") (class "Default")
      (node (ref "MT1") (pin "11") (pinfunction "RESV_11") (pintype "passive+no_connect"))
    )
  )
)
